# RGBM-03.net
KiCad netlist of a schematic drawn in Altium Designer
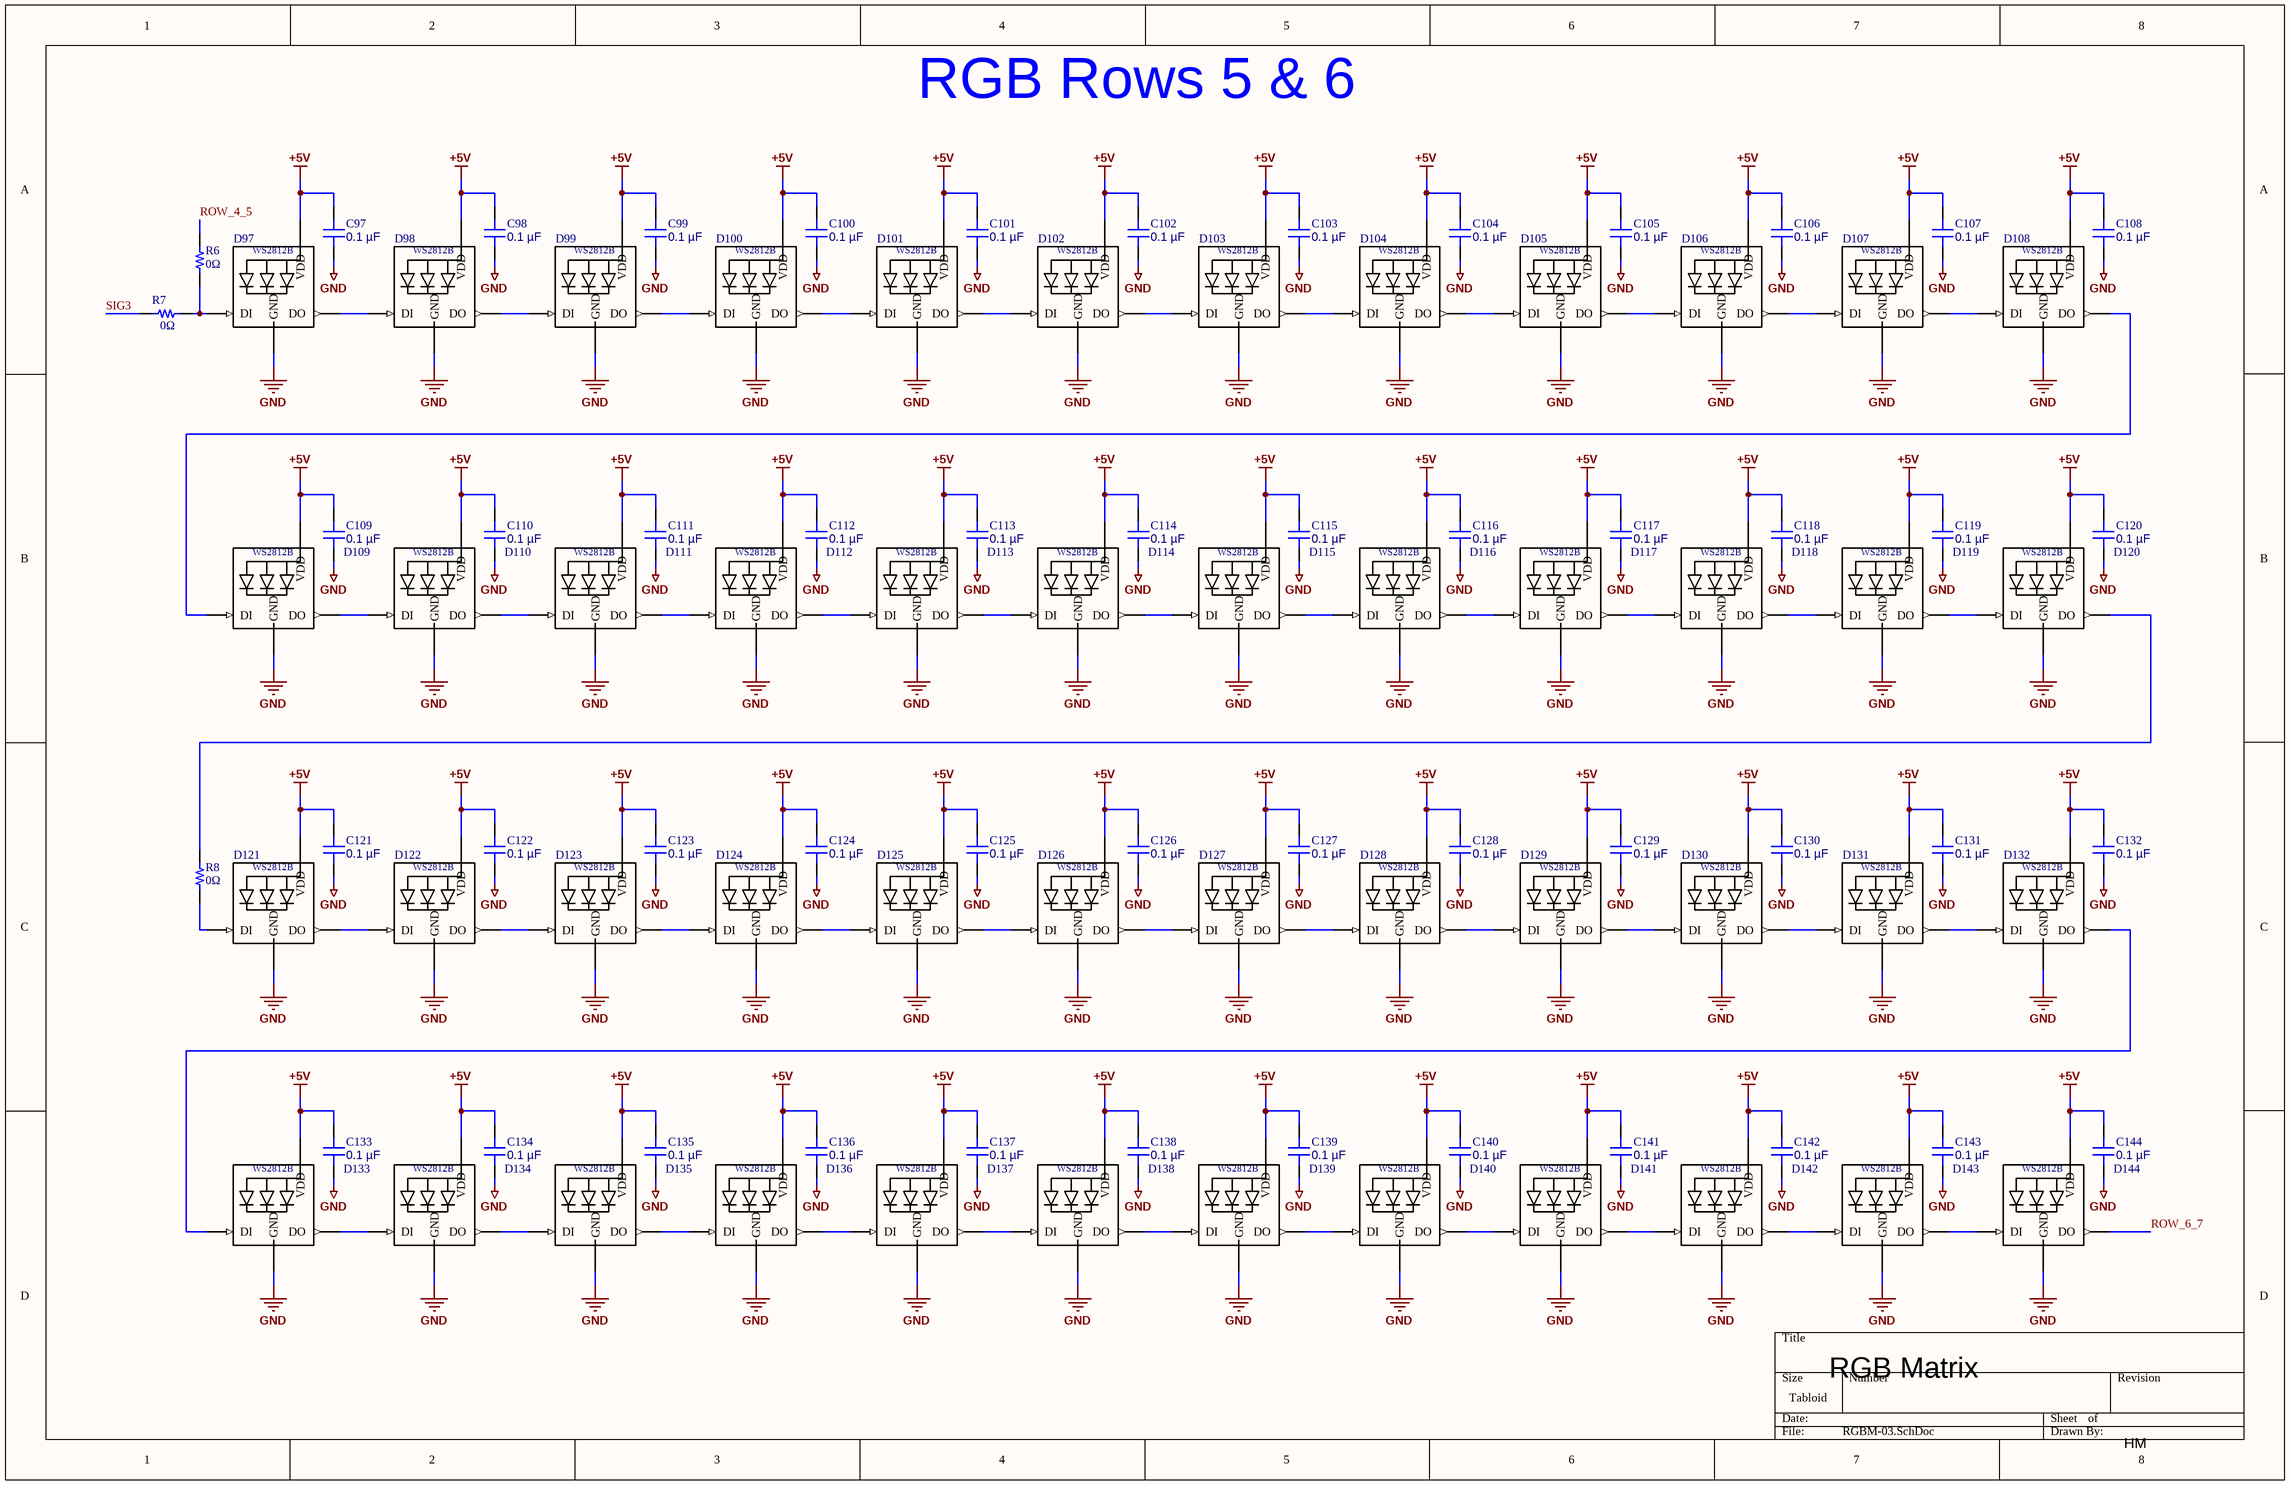
[diagram p0: RGBM-03.SchDoc]

(export (version "E")
  (design (tool "Eeschema 10.0.6"))
  (components
    (comp (ref "C97")
      (value "0.1 µF")
      (footprint "CAP 0603_1608")
      (description "CAP CER 0.1UF 50V X7R 0603")
      (fields
        (field (name "PART NUMBER") "C0603C104K5RAC7411")
        (field (name "CAPACITANCE") "0.1 µF")
        (field (name "MANUFACTURER") "KEMET")
      )
      (libsource (lib "Celestial Altium Library - altium_library") (part "Capacitor"))
    )
    (comp (ref "C98")
      (value "0.1 µF")
      (footprint "CAP 0603_1608")
      (description "CAP CER 0.1UF 50V X7R 0603")
      (fields
        (field (name "PART NUMBER") "C0603C104K5RAC7411")
        (field (name "CAPACITANCE") "0.1 µF")
        (field (name "MANUFACTURER") "KEMET")
      )
      (libsource (lib "Celestial Altium Library - altium_library") (part "Capacitor"))
    )
    (comp (ref "C99")
      (value "0.1 µF")
      (footprint "CAP 0603_1608")
      (description "CAP CER 0.1UF 50V X7R 0603")
      (fields
        (field (name "PART NUMBER") "C0603C104K5RAC7411")
        (field (name "CAPACITANCE") "0.1 µF")
        (field (name "MANUFACTURER") "KEMET")
      )
      (libsource (lib "Celestial Altium Library - altium_library") (part "Capacitor"))
    )
    (comp (ref "C100")
      (value "0.1 µF")
      (footprint "CAP 0603_1608")
      (description "CAP CER 0.1UF 50V X7R 0603")
      (fields
        (field (name "PART NUMBER") "C0603C104K5RAC7411")
        (field (name "CAPACITANCE") "0.1 µF")
        (field (name "MANUFACTURER") "KEMET")
      )
      (libsource (lib "Celestial Altium Library - altium_library") (part "Capacitor"))
    )
    (comp (ref "C101")
      (value "0.1 µF")
      (footprint "CAP 0603_1608")
      (description "CAP CER 0.1UF 50V X7R 0603")
      (fields
        (field (name "PART NUMBER") "C0603C104K5RAC7411")
        (field (name "CAPACITANCE") "0.1 µF")
        (field (name "MANUFACTURER") "KEMET")
      )
      (libsource (lib "Celestial Altium Library - altium_library") (part "Capacitor"))
    )
    (comp (ref "C102")
      (value "0.1 µF")
      (footprint "CAP 0603_1608")
      (description "CAP CER 0.1UF 50V X7R 0603")
      (fields
        (field (name "PART NUMBER") "C0603C104K5RAC7411")
        (field (name "CAPACITANCE") "0.1 µF")
        (field (name "MANUFACTURER") "KEMET")
      )
      (libsource (lib "Celestial Altium Library - altium_library") (part "Capacitor"))
    )
    (comp (ref "C103")
      (value "0.1 µF")
      (footprint "CAP 0603_1608")
      (description "CAP CER 0.1UF 50V X7R 0603")
      (fields
        (field (name "PART NUMBER") "C0603C104K5RAC7411")
        (field (name "CAPACITANCE") "0.1 µF")
        (field (name "MANUFACTURER") "KEMET")
      )
      (libsource (lib "Celestial Altium Library - altium_library") (part "Capacitor"))
    )
    (comp (ref "C104")
      (value "0.1 µF")
      (footprint "CAP 0603_1608")
      (description "CAP CER 0.1UF 50V X7R 0603")
      (fields
        (field (name "PART NUMBER") "C0603C104K5RAC7411")
        (field (name "CAPACITANCE") "0.1 µF")
        (field (name "MANUFACTURER") "KEMET")
      )
      (libsource (lib "Celestial Altium Library - altium_library") (part "Capacitor"))
    )
    (comp (ref "C105")
      (value "0.1 µF")
      (footprint "CAP 0603_1608")
      (description "CAP CER 0.1UF 50V X7R 0603")
      (fields
        (field (name "PART NUMBER") "C0603C104K5RAC7411")
        (field (name "CAPACITANCE") "0.1 µF")
        (field (name "MANUFACTURER") "KEMET")
      )
      (libsource (lib "Celestial Altium Library - altium_library") (part "Capacitor"))
    )
    (comp (ref "C106")
      (value "0.1 µF")
      (footprint "CAP 0603_1608")
      (description "CAP CER 0.1UF 50V X7R 0603")
      (fields
        (field (name "PART NUMBER") "C0603C104K5RAC7411")
        (field (name "CAPACITANCE") "0.1 µF")
        (field (name "MANUFACTURER") "KEMET")
      )
      (libsource (lib "Celestial Altium Library - altium_library") (part "Capacitor"))
    )
    (comp (ref "C107")
      (value "0.1 µF")
      (footprint "CAP 0603_1608")
      (description "CAP CER 0.1UF 50V X7R 0603")
      (fields
        (field (name "PART NUMBER") "C0603C104K5RAC7411")
        (field (name "CAPACITANCE") "0.1 µF")
        (field (name "MANUFACTURER") "KEMET")
      )
      (libsource (lib "Celestial Altium Library - altium_library") (part "Capacitor"))
    )
    (comp (ref "C108")
      (value "0.1 µF")
      (footprint "CAP 0603_1608")
      (description "CAP CER 0.1UF 50V X7R 0603")
      (fields
        (field (name "PART NUMBER") "C0603C104K5RAC7411")
        (field (name "CAPACITANCE") "0.1 µF")
        (field (name "MANUFACTURER") "KEMET")
      )
      (libsource (lib "Celestial Altium Library - altium_library") (part "Capacitor"))
    )
    (comp (ref "C109")
      (value "0.1 µF")
      (footprint "CAP 0603_1608")
      (description "CAP CER 0.1UF 50V X7R 0603")
      (fields
        (field (name "PART NUMBER") "C0603C104K5RAC7411")
        (field (name "CAPACITANCE") "0.1 µF")
        (field (name "MANUFACTURER") "KEMET")
      )
      (libsource (lib "Celestial Altium Library - altium_library") (part "Capacitor"))
    )
    (comp (ref "C110")
      (value "0.1 µF")
      (footprint "CAP 0603_1608")
      (description "CAP CER 0.1UF 50V X7R 0603")
      (fields
        (field (name "PART NUMBER") "C0603C104K5RAC7411")
        (field (name "CAPACITANCE") "0.1 µF")
        (field (name "MANUFACTURER") "KEMET")
      )
      (libsource (lib "Celestial Altium Library - altium_library") (part "Capacitor"))
    )
    (comp (ref "C111")
      (value "0.1 µF")
      (footprint "CAP 0603_1608")
      (description "CAP CER 0.1UF 50V X7R 0603")
      (fields
        (field (name "PART NUMBER") "C0603C104K5RAC7411")
        (field (name "CAPACITANCE") "0.1 µF")
        (field (name "MANUFACTURER") "KEMET")
      )
      (libsource (lib "Celestial Altium Library - altium_library") (part "Capacitor"))
    )
    (comp (ref "C112")
      (value "0.1 µF")
      (footprint "CAP 0603_1608")
      (description "CAP CER 0.1UF 50V X7R 0603")
      (fields
        (field (name "PART NUMBER") "C0603C104K5RAC7411")
        (field (name "CAPACITANCE") "0.1 µF")
        (field (name "MANUFACTURER") "KEMET")
      )
      (libsource (lib "Celestial Altium Library - altium_library") (part "Capacitor"))
    )
    (comp (ref "C113")
      (value "0.1 µF")
      (footprint "CAP 0603_1608")
      (description "CAP CER 0.1UF 50V X7R 0603")
      (fields
        (field (name "PART NUMBER") "C0603C104K5RAC7411")
        (field (name "CAPACITANCE") "0.1 µF")
        (field (name "MANUFACTURER") "KEMET")
      )
      (libsource (lib "Celestial Altium Library - altium_library") (part "Capacitor"))
    )
    (comp (ref "C114")
      (value "0.1 µF")
      (footprint "CAP 0603_1608")
      (description "CAP CER 0.1UF 50V X7R 0603")
      (fields
        (field (name "PART NUMBER") "C0603C104K5RAC7411")
        (field (name "CAPACITANCE") "0.1 µF")
        (field (name "MANUFACTURER") "KEMET")
      )
      (libsource (lib "Celestial Altium Library - altium_library") (part "Capacitor"))
    )
    (comp (ref "C115")
      (value "0.1 µF")
      (footprint "CAP 0603_1608")
      (description "CAP CER 0.1UF 50V X7R 0603")
      (fields
        (field (name "PART NUMBER") "C0603C104K5RAC7411")
        (field (name "CAPACITANCE") "0.1 µF")
        (field (name "MANUFACTURER") "KEMET")
      )
      (libsource (lib "Celestial Altium Library - altium_library") (part "Capacitor"))
    )
    (comp (ref "C116")
      (value "0.1 µF")
      (footprint "CAP 0603_1608")
      (description "CAP CER 0.1UF 50V X7R 0603")
      (fields
        (field (name "PART NUMBER") "C0603C104K5RAC7411")
        (field (name "CAPACITANCE") "0.1 µF")
        (field (name "MANUFACTURER") "KEMET")
      )
      (libsource (lib "Celestial Altium Library - altium_library") (part "Capacitor"))
    )
    (comp (ref "C117")
      (value "0.1 µF")
      (footprint "CAP 0603_1608")
      (description "CAP CER 0.1UF 50V X7R 0603")
      (fields
        (field (name "PART NUMBER") "C0603C104K5RAC7411")
        (field (name "CAPACITANCE") "0.1 µF")
        (field (name "MANUFACTURER") "KEMET")
      )
      (libsource (lib "Celestial Altium Library - altium_library") (part "Capacitor"))
    )
    (comp (ref "C118")
      (value "0.1 µF")
      (footprint "CAP 0603_1608")
      (description "CAP CER 0.1UF 50V X7R 0603")
      (fields
        (field (name "PART NUMBER") "C0603C104K5RAC7411")
        (field (name "CAPACITANCE") "0.1 µF")
        (field (name "MANUFACTURER") "KEMET")
      )
      (libsource (lib "Celestial Altium Library - altium_library") (part "Capacitor"))
    )
    (comp (ref "C119")
      (value "0.1 µF")
      (footprint "CAP 0603_1608")
      (description "CAP CER 0.1UF 50V X7R 0603")
      (fields
        (field (name "PART NUMBER") "C0603C104K5RAC7411")
        (field (name "CAPACITANCE") "0.1 µF")
        (field (name "MANUFACTURER") "KEMET")
      )
      (libsource (lib "Celestial Altium Library - altium_library") (part "Capacitor"))
    )
    (comp (ref "C120")
      (value "0.1 µF")
      (footprint "CAP 0603_1608")
      (description "CAP CER 0.1UF 50V X7R 0603")
      (fields
        (field (name "PART NUMBER") "C0603C104K5RAC7411")
        (field (name "CAPACITANCE") "0.1 µF")
        (field (name "MANUFACTURER") "KEMET")
      )
      (libsource (lib "Celestial Altium Library - altium_library") (part "Capacitor"))
    )
    (comp (ref "C121")
      (value "0.1 µF")
      (footprint "CAP 0603_1608")
      (description "CAP CER 0.1UF 50V X7R 0603")
      (fields
        (field (name "PART NUMBER") "C0603C104K5RAC7411")
        (field (name "CAPACITANCE") "0.1 µF")
        (field (name "MANUFACTURER") "KEMET")
      )
      (libsource (lib "Celestial Altium Library - altium_library") (part "Capacitor"))
    )
    (comp (ref "C122")
      (value "0.1 µF")
      (footprint "CAP 0603_1608")
      (description "CAP CER 0.1UF 50V X7R 0603")
      (fields
        (field (name "PART NUMBER") "C0603C104K5RAC7411")
        (field (name "CAPACITANCE") "0.1 µF")
        (field (name "MANUFACTURER") "KEMET")
      )
      (libsource (lib "Celestial Altium Library - altium_library") (part "Capacitor"))
    )
    (comp (ref "C123")
      (value "0.1 µF")
      (footprint "CAP 0603_1608")
      (description "CAP CER 0.1UF 50V X7R 0603")
      (fields
        (field (name "PART NUMBER") "C0603C104K5RAC7411")
        (field (name "CAPACITANCE") "0.1 µF")
        (field (name "MANUFACTURER") "KEMET")
      )
      (libsource (lib "Celestial Altium Library - altium_library") (part "Capacitor"))
    )
    (comp (ref "C124")
      (value "0.1 µF")
      (footprint "CAP 0603_1608")
      (description "CAP CER 0.1UF 50V X7R 0603")
      (fields
        (field (name "PART NUMBER") "C0603C104K5RAC7411")
        (field (name "CAPACITANCE") "0.1 µF")
        (field (name "MANUFACTURER") "KEMET")
      )
      (libsource (lib "Celestial Altium Library - altium_library") (part "Capacitor"))
    )
    (comp (ref "C125")
      (value "0.1 µF")
      (footprint "CAP 0603_1608")
      (description "CAP CER 0.1UF 50V X7R 0603")
      (fields
        (field (name "PART NUMBER") "C0603C104K5RAC7411")
        (field (name "CAPACITANCE") "0.1 µF")
        (field (name "MANUFACTURER") "KEMET")
      )
      (libsource (lib "Celestial Altium Library - altium_library") (part "Capacitor"))
    )
    (comp (ref "C126")
      (value "0.1 µF")
      (footprint "CAP 0603_1608")
      (description "CAP CER 0.1UF 50V X7R 0603")
      (fields
        (field (name "PART NUMBER") "C0603C104K5RAC7411")
        (field (name "CAPACITANCE") "0.1 µF")
        (field (name "MANUFACTURER") "KEMET")
      )
      (libsource (lib "Celestial Altium Library - altium_library") (part "Capacitor"))
    )
    (comp (ref "C127")
      (value "0.1 µF")
      (footprint "CAP 0603_1608")
      (description "CAP CER 0.1UF 50V X7R 0603")
      (fields
        (field (name "PART NUMBER") "C0603C104K5RAC7411")
        (field (name "CAPACITANCE") "0.1 µF")
        (field (name "MANUFACTURER") "KEMET")
      )
      (libsource (lib "Celestial Altium Library - altium_library") (part "Capacitor"))
    )
    (comp (ref "C128")
      (value "0.1 µF")
      (footprint "CAP 0603_1608")
      (description "CAP CER 0.1UF 50V X7R 0603")
      (fields
        (field (name "PART NUMBER") "C0603C104K5RAC7411")
        (field (name "CAPACITANCE") "0.1 µF")
        (field (name "MANUFACTURER") "KEMET")
      )
      (libsource (lib "Celestial Altium Library - altium_library") (part "Capacitor"))
    )
    (comp (ref "C129")
      (value "0.1 µF")
      (footprint "CAP 0603_1608")
      (description "CAP CER 0.1UF 50V X7R 0603")
      (fields
        (field (name "PART NUMBER") "C0603C104K5RAC7411")
        (field (name "CAPACITANCE") "0.1 µF")
        (field (name "MANUFACTURER") "KEMET")
      )
      (libsource (lib "Celestial Altium Library - altium_library") (part "Capacitor"))
    )
    (comp (ref "C130")
      (value "0.1 µF")
      (footprint "CAP 0603_1608")
      (description "CAP CER 0.1UF 50V X7R 0603")
      (fields
        (field (name "PART NUMBER") "C0603C104K5RAC7411")
        (field (name "CAPACITANCE") "0.1 µF")
        (field (name "MANUFACTURER") "KEMET")
      )
      (libsource (lib "Celestial Altium Library - altium_library") (part "Capacitor"))
    )
    (comp (ref "C131")
      (value "0.1 µF")
      (footprint "CAP 0603_1608")
      (description "CAP CER 0.1UF 50V X7R 0603")
      (fields
        (field (name "PART NUMBER") "C0603C104K5RAC7411")
        (field (name "CAPACITANCE") "0.1 µF")
        (field (name "MANUFACTURER") "KEMET")
      )
      (libsource (lib "Celestial Altium Library - altium_library") (part "Capacitor"))
    )
    (comp (ref "C132")
      (value "0.1 µF")
      (footprint "CAP 0603_1608")
      (description "CAP CER 0.1UF 50V X7R 0603")
      (fields
        (field (name "PART NUMBER") "C0603C104K5RAC7411")
        (field (name "CAPACITANCE") "0.1 µF")
        (field (name "MANUFACTURER") "KEMET")
      )
      (libsource (lib "Celestial Altium Library - altium_library") (part "Capacitor"))
    )
    (comp (ref "C133")
      (value "0.1 µF")
      (footprint "CAP 0603_1608")
      (description "CAP CER 0.1UF 50V X7R 0603")
      (fields
        (field (name "PART NUMBER") "C0603C104K5RAC7411")
        (field (name "CAPACITANCE") "0.1 µF")
        (field (name "MANUFACTURER") "KEMET")
      )
      (libsource (lib "Celestial Altium Library - altium_library") (part "Capacitor"))
    )
    (comp (ref "C134")
      (value "0.1 µF")
      (footprint "CAP 0603_1608")
      (description "CAP CER 0.1UF 50V X7R 0603")
      (fields
        (field (name "PART NUMBER") "C0603C104K5RAC7411")
        (field (name "CAPACITANCE") "0.1 µF")
        (field (name "MANUFACTURER") "KEMET")
      )
      (libsource (lib "Celestial Altium Library - altium_library") (part "Capacitor"))
    )
    (comp (ref "C135")
      (value "0.1 µF")
      (footprint "CAP 0603_1608")
      (description "CAP CER 0.1UF 50V X7R 0603")
      (fields
        (field (name "PART NUMBER") "C0603C104K5RAC7411")
        (field (name "CAPACITANCE") "0.1 µF")
        (field (name "MANUFACTURER") "KEMET")
      )
      (libsource (lib "Celestial Altium Library - altium_library") (part "Capacitor"))
    )
    (comp (ref "C136")
      (value "0.1 µF")
      (footprint "CAP 0603_1608")
      (description "CAP CER 0.1UF 50V X7R 0603")
      (fields
        (field (name "PART NUMBER") "C0603C104K5RAC7411")
        (field (name "CAPACITANCE") "0.1 µF")
        (field (name "MANUFACTURER") "KEMET")
      )
      (libsource (lib "Celestial Altium Library - altium_library") (part "Capacitor"))
    )
    (comp (ref "C137")
      (value "0.1 µF")
      (footprint "CAP 0603_1608")
      (description "CAP CER 0.1UF 50V X7R 0603")
      (fields
        (field (name "PART NUMBER") "C0603C104K5RAC7411")
        (field (name "CAPACITANCE") "0.1 µF")
        (field (name "MANUFACTURER") "KEMET")
      )
      (libsource (lib "Celestial Altium Library - altium_library") (part "Capacitor"))
    )
    (comp (ref "C138")
      (value "0.1 µF")
      (footprint "CAP 0603_1608")
      (description "CAP CER 0.1UF 50V X7R 0603")
      (fields
        (field (name "PART NUMBER") "C0603C104K5RAC7411")
        (field (name "CAPACITANCE") "0.1 µF")
        (field (name "MANUFACTURER") "KEMET")
      )
      (libsource (lib "Celestial Altium Library - altium_library") (part "Capacitor"))
    )
    (comp (ref "C139")
      (value "0.1 µF")
      (footprint "CAP 0603_1608")
      (description "CAP CER 0.1UF 50V X7R 0603")
      (fields
        (field (name "PART NUMBER") "C0603C104K5RAC7411")
        (field (name "CAPACITANCE") "0.1 µF")
        (field (name "MANUFACTURER") "KEMET")
      )
      (libsource (lib "Celestial Altium Library - altium_library") (part "Capacitor"))
    )
    (comp (ref "C140")
      (value "0.1 µF")
      (footprint "CAP 0603_1608")
      (description "CAP CER 0.1UF 50V X7R 0603")
      (fields
        (field (name "PART NUMBER") "C0603C104K5RAC7411")
        (field (name "CAPACITANCE") "0.1 µF")
        (field (name "MANUFACTURER") "KEMET")
      )
      (libsource (lib "Celestial Altium Library - altium_library") (part "Capacitor"))
    )
    (comp (ref "C141")
      (value "0.1 µF")
      (footprint "CAP 0603_1608")
      (description "CAP CER 0.1UF 50V X7R 0603")
      (fields
        (field (name "PART NUMBER") "C0603C104K5RAC7411")
        (field (name "CAPACITANCE") "0.1 µF")
        (field (name "MANUFACTURER") "KEMET")
      )
      (libsource (lib "Celestial Altium Library - altium_library") (part "Capacitor"))
    )
    (comp (ref "C142")
      (value "0.1 µF")
      (footprint "CAP 0603_1608")
      (description "CAP CER 0.1UF 50V X7R 0603")
      (fields
        (field (name "PART NUMBER") "C0603C104K5RAC7411")
        (field (name "CAPACITANCE") "0.1 µF")
        (field (name "MANUFACTURER") "KEMET")
      )
      (libsource (lib "Celestial Altium Library - altium_library") (part "Capacitor"))
    )
    (comp (ref "C143")
      (value "0.1 µF")
      (footprint "CAP 0603_1608")
      (description "CAP CER 0.1UF 50V X7R 0603")
      (fields
        (field (name "PART NUMBER") "C0603C104K5RAC7411")
        (field (name "CAPACITANCE") "0.1 µF")
        (field (name "MANUFACTURER") "KEMET")
      )
      (libsource (lib "Celestial Altium Library - altium_library") (part "Capacitor"))
    )
    (comp (ref "C144")
      (value "0.1 µF")
      (footprint "CAP 0603_1608")
      (description "CAP CER 0.1UF 50V X7R 0603")
      (fields
        (field (name "PART NUMBER") "C0603C104K5RAC7411")
        (field (name "CAPACITANCE") "0.1 µF")
        (field (name "MANUFACTURER") "KEMET")
      )
      (libsource (lib "Celestial Altium Library - altium_library") (part "Capacitor"))
    )
    (comp (ref "D97")
      (value "WS2812B")
      (footprint "*WS2812B_WS2812B(Primary)")
      (description "Intelligent control LED integrated light source")
      (fields (field (name "MF") "Worldsemi"))
      (libsource (lib "WS2812B") (part "WS2812B"))
    )
    (comp (ref "D98")
      (value "WS2812B")
      (footprint "*WS2812B_WS2812B(Primary)")
      (description "Intelligent control LED integrated light source")
      (fields (field (name "MF") "Worldsemi"))
      (libsource (lib "WS2812B") (part "WS2812B"))
    )
    (comp (ref "D99")
      (value "WS2812B")
      (footprint "*WS2812B_WS2812B(Primary)")
      (description "Intelligent control LED integrated light source")
      (fields (field (name "MF") "Worldsemi"))
      (libsource (lib "WS2812B") (part "WS2812B"))
    )
    (comp (ref "D100")
      (value "WS2812B")
      (footprint "*WS2812B_WS2812B(Primary)")
      (description "Intelligent control LED integrated light source")
      (fields (field (name "MF") "Worldsemi"))
      (libsource (lib "WS2812B") (part "WS2812B"))
    )
    (comp (ref "D101")
      (value "WS2812B")
      (footprint "*WS2812B_WS2812B(Primary)")
      (description "Intelligent control LED integrated light source")
      (fields (field (name "MF") "Worldsemi"))
      (libsource (lib "WS2812B") (part "WS2812B"))
    )
    (comp (ref "D102")
      (value "WS2812B")
      (footprint "*WS2812B_WS2812B(Primary)")
      (description "Intelligent control LED integrated light source")
      (fields (field (name "MF") "Worldsemi"))
      (libsource (lib "WS2812B") (part "WS2812B"))
    )
    (comp (ref "D103")
      (value "WS2812B")
      (footprint "*WS2812B_WS2812B(Primary)")
      (description "Intelligent control LED integrated light source")
      (fields (field (name "MF") "Worldsemi"))
      (libsource (lib "WS2812B") (part "WS2812B"))
    )
    (comp (ref "D104")
      (value "WS2812B")
      (footprint "*WS2812B_WS2812B(Primary)")
      (description "Intelligent control LED integrated light source")
      (fields (field (name "MF") "Worldsemi"))
      (libsource (lib "WS2812B") (part "WS2812B"))
    )
    (comp (ref "D105")
      (value "WS2812B")
      (footprint "*WS2812B_WS2812B(Primary)")
      (description "Intelligent control LED integrated light source")
      (fields (field (name "MF") "Worldsemi"))
      (libsource (lib "WS2812B") (part "WS2812B"))
    )
    (comp (ref "D106")
      (value "WS2812B")
      (footprint "*WS2812B_WS2812B(Primary)")
      (description "Intelligent control LED integrated light source")
      (fields (field (name "MF") "Worldsemi"))
      (libsource (lib "WS2812B") (part "WS2812B"))
    )
    (comp (ref "D107")
      (value "WS2812B")
      (footprint "*WS2812B_WS2812B(Primary)")
      (description "Intelligent control LED integrated light source")
      (fields (field (name "MF") "Worldsemi"))
      (libsource (lib "WS2812B") (part "WS2812B"))
    )
    (comp (ref "D108")
      (value "WS2812B")
      (footprint "*WS2812B_WS2812B(Primary)")
      (description "Intelligent control LED integrated light source")
      (fields (field (name "MF") "Worldsemi"))
      (libsource (lib "WS2812B") (part "WS2812B"))
    )
    (comp (ref "D109")
      (value "WS2812B")
      (footprint "*WS2812B_WS2812B(Primary)")
      (description "Intelligent control LED integrated light source")
      (fields (field (name "MF") "Worldsemi"))
      (libsource (lib "WS2812B") (part "WS2812B"))
    )
    (comp (ref "D110")
      (value "WS2812B")
      (footprint "*WS2812B_WS2812B(Primary)")
      (description "Intelligent control LED integrated light source")
      (fields (field (name "MF") "Worldsemi"))
      (libsource (lib "WS2812B") (part "WS2812B"))
    )
    (comp (ref "D111")
      (value "WS2812B")
      (footprint "*WS2812B_WS2812B(Primary)")
      (description "Intelligent control LED integrated light source")
      (fields (field (name "MF") "Worldsemi"))
      (libsource (lib "WS2812B") (part "WS2812B"))
    )
    (comp (ref "D112")
      (value "WS2812B")
      (footprint "*WS2812B_WS2812B(Primary)")
      (description "Intelligent control LED integrated light source")
      (fields (field (name "MF") "Worldsemi"))
      (libsource (lib "WS2812B") (part "WS2812B"))
    )
    (comp (ref "D113")
      (value "WS2812B")
      (footprint "*WS2812B_WS2812B(Primary)")
      (description "Intelligent control LED integrated light source")
      (fields (field (name "MF") "Worldsemi"))
      (libsource (lib "WS2812B") (part "WS2812B"))
    )
    (comp (ref "D114")
      (value "WS2812B")
      (footprint "*WS2812B_WS2812B(Primary)")
      (description "Intelligent control LED integrated light source")
      (fields (field (name "MF") "Worldsemi"))
      (libsource (lib "WS2812B") (part "WS2812B"))
    )
    (comp (ref "D115")
      (value "WS2812B")
      (footprint "*WS2812B_WS2812B(Primary)")
      (description "Intelligent control LED integrated light source")
      (fields (field (name "MF") "Worldsemi"))
      (libsource (lib "WS2812B") (part "WS2812B"))
    )
    (comp (ref "D116")
      (value "WS2812B")
      (footprint "*WS2812B_WS2812B(Primary)")
      (description "Intelligent control LED integrated light source")
      (fields (field (name "MF") "Worldsemi"))
      (libsource (lib "WS2812B") (part "WS2812B"))
    )
    (comp (ref "D117")
      (value "WS2812B")
      (footprint "*WS2812B_WS2812B(Primary)")
      (description "Intelligent control LED integrated light source")
      (fields (field (name "MF") "Worldsemi"))
      (libsource (lib "WS2812B") (part "WS2812B"))
    )
    (comp (ref "D118")
      (value "WS2812B")
      (footprint "*WS2812B_WS2812B(Primary)")
      (description "Intelligent control LED integrated light source")
      (fields (field (name "MF") "Worldsemi"))
      (libsource (lib "WS2812B") (part "WS2812B"))
    )
    (comp (ref "D119")
      (value "WS2812B")
      (footprint "*WS2812B_WS2812B(Primary)")
      (description "Intelligent control LED integrated light source")
      (fields (field (name "MF") "Worldsemi"))
      (libsource (lib "WS2812B") (part "WS2812B"))
    )
    (comp (ref "D120")
      (value "WS2812B")
      (footprint "*WS2812B_WS2812B(Primary)")
      (description "Intelligent control LED integrated light source")
      (fields (field (name "MF") "Worldsemi"))
      (libsource (lib "WS2812B") (part "WS2812B"))
    )
    (comp (ref "D121")
      (value "WS2812B")
      (footprint "*WS2812B_WS2812B(Primary)")
      (description "Intelligent control LED integrated light source")
      (fields (field (name "MF") "Worldsemi"))
      (libsource (lib "WS2812B") (part "WS2812B"))
    )
    (comp (ref "D122")
      (value "WS2812B")
      (footprint "*WS2812B_WS2812B(Primary)")
      (description "Intelligent control LED integrated light source")
      (fields (field (name "MF") "Worldsemi"))
      (libsource (lib "WS2812B") (part "WS2812B"))
    )
    (comp (ref "D123")
      (value "WS2812B")
      (footprint "*WS2812B_WS2812B(Primary)")
      (description "Intelligent control LED integrated light source")
      (fields (field (name "MF") "Worldsemi"))
      (libsource (lib "WS2812B") (part "WS2812B"))
    )
    (comp (ref "D124")
      (value "WS2812B")
      (footprint "*WS2812B_WS2812B(Primary)")
      (description "Intelligent control LED integrated light source")
      (fields (field (name "MF") "Worldsemi"))
      (libsource (lib "WS2812B") (part "WS2812B"))
    )
    (comp (ref "D125")
      (value "WS2812B")
      (footprint "*WS2812B_WS2812B(Primary)")
      (description "Intelligent control LED integrated light source")
      (fields (field (name "MF") "Worldsemi"))
      (libsource (lib "WS2812B") (part "WS2812B"))
    )
    (comp (ref "D126")
      (value "WS2812B")
      (footprint "*WS2812B_WS2812B(Primary)")
      (description "Intelligent control LED integrated light source")
      (fields (field (name "MF") "Worldsemi"))
      (libsource (lib "WS2812B") (part "WS2812B"))
    )
    (comp (ref "D127")
      (value "WS2812B")
      (footprint "*WS2812B_WS2812B(Primary)")
      (description "Intelligent control LED integrated light source")
      (fields (field (name "MF") "Worldsemi"))
      (libsource (lib "WS2812B") (part "WS2812B"))
    )
    (comp (ref "D128")
      (value "WS2812B")
      (footprint "*WS2812B_WS2812B(Primary)")
      (description "Intelligent control LED integrated light source")
      (fields (field (name "MF") "Worldsemi"))
      (libsource (lib "WS2812B") (part "WS2812B"))
    )
    (comp (ref "D129")
      (value "WS2812B")
      (footprint "*WS2812B_WS2812B(Primary)")
      (description "Intelligent control LED integrated light source")
      (fields (field (name "MF") "Worldsemi"))
      (libsource (lib "WS2812B") (part "WS2812B"))
    )
    (comp (ref "D130")
      (value "WS2812B")
      (footprint "*WS2812B_WS2812B(Primary)")
      (description "Intelligent control LED integrated light source")
      (fields (field (name "MF") "Worldsemi"))
      (libsource (lib "WS2812B") (part "WS2812B"))
    )
    (comp (ref "D131")
      (value "WS2812B")
      (footprint "*WS2812B_WS2812B(Primary)")
      (description "Intelligent control LED integrated light source")
      (fields (field (name "MF") "Worldsemi"))
      (libsource (lib "WS2812B") (part "WS2812B"))
    )
    (comp (ref "D132")
      (value "WS2812B")
      (footprint "*WS2812B_WS2812B(Primary)")
      (description "Intelligent control LED integrated light source")
      (fields (field (name "MF") "Worldsemi"))
      (libsource (lib "WS2812B") (part "WS2812B"))
    )
    (comp (ref "D133")
      (value "WS2812B")
      (footprint "*WS2812B_WS2812B(Primary)")
      (description "Intelligent control LED integrated light source")
      (fields (field (name "MF") "Worldsemi"))
      (libsource (lib "WS2812B") (part "WS2812B"))
    )
    (comp (ref "D134")
      (value "WS2812B")
      (footprint "*WS2812B_WS2812B(Primary)")
      (description "Intelligent control LED integrated light source")
      (fields (field (name "MF") "Worldsemi"))
      (libsource (lib "WS2812B") (part "WS2812B"))
    )
    (comp (ref "D135")
      (value "WS2812B")
      (footprint "*WS2812B_WS2812B(Primary)")
      (description "Intelligent control LED integrated light source")
      (fields (field (name "MF") "Worldsemi"))
      (libsource (lib "WS2812B") (part "WS2812B"))
    )
    (comp (ref "D136")
      (value "WS2812B")
      (footprint "*WS2812B_WS2812B(Primary)")
      (description "Intelligent control LED integrated light source")
      (fields (field (name "MF") "Worldsemi"))
      (libsource (lib "WS2812B") (part "WS2812B"))
    )
    (comp (ref "D137")
      (value "WS2812B")
      (footprint "*WS2812B_WS2812B(Primary)")
      (description "Intelligent control LED integrated light source")
      (fields (field (name "MF") "Worldsemi"))
      (libsource (lib "WS2812B") (part "WS2812B"))
    )
    (comp (ref "D138")
      (value "WS2812B")
      (footprint "*WS2812B_WS2812B(Primary)")
      (description "Intelligent control LED integrated light source")
      (fields (field (name "MF") "Worldsemi"))
      (libsource (lib "WS2812B") (part "WS2812B"))
    )
    (comp (ref "D139")
      (value "WS2812B")
      (footprint "*WS2812B_WS2812B(Primary)")
      (description "Intelligent control LED integrated light source")
      (fields (field (name "MF") "Worldsemi"))
      (libsource (lib "WS2812B") (part "WS2812B"))
    )
    (comp (ref "D140")
      (value "WS2812B")
      (footprint "*WS2812B_WS2812B(Primary)")
      (description "Intelligent control LED integrated light source")
      (fields (field (name "MF") "Worldsemi"))
      (libsource (lib "WS2812B") (part "WS2812B"))
    )
    (comp (ref "D141")
      (value "WS2812B")
      (footprint "*WS2812B_WS2812B(Primary)")
      (description "Intelligent control LED integrated light source")
      (fields (field (name "MF") "Worldsemi"))
      (libsource (lib "WS2812B") (part "WS2812B"))
    )
    (comp (ref "D142")
      (value "WS2812B")
      (footprint "*WS2812B_WS2812B(Primary)")
      (description "Intelligent control LED integrated light source")
      (fields (field (name "MF") "Worldsemi"))
      (libsource (lib "WS2812B") (part "WS2812B"))
    )
    (comp (ref "D143")
      (value "WS2812B")
      (footprint "*WS2812B_WS2812B(Primary)")
      (description "Intelligent control LED integrated light source")
      (fields (field (name "MF") "Worldsemi"))
      (libsource (lib "WS2812B") (part "WS2812B"))
    )
    (comp (ref "D144")
      (value "WS2812B")
      (footprint "*WS2812B_WS2812B(Primary)")
      (description "Intelligent control LED integrated light source")
      (fields (field (name "MF") "Worldsemi"))
      (libsource (lib "WS2812B") (part "WS2812B"))
    )
    (comp (ref "R6")
      (value "0Ω")
      (footprint "RES 0603_1608")
      (description "RES SMD 0 OHM JUMPER 0603")
      (fields (field (name "PART NUMBER") "YJP1608-R001") (field (name "MANUFACTURER") "Susumu"))
      (libsource (lib "Celestial Altium Library - altium_library") (part "Resistor"))
    )
    (comp (ref "R7")
      (value "0Ω")
      (footprint "RES 0603_1608")
      (description "RES SMD 0 OHM JUMPER 0603")
      (fields (field (name "PART NUMBER") "YJP1608-R001") (field (name "MANUFACTURER") "Susumu"))
      (libsource (lib "Celestial Altium Library - altium_library") (part "Resistor"))
    )
    (comp (ref "R8")
      (value "0Ω")
      (footprint "RES 0603_1608")
      (description "RES SMD 0 OHM JUMPER 0603")
      (fields (field (name "PART NUMBER") "YJP1608-R001") (field (name "MANUFACTURER") "Susumu"))
      (libsource (lib "Celestial Altium Library - altium_library") (part "Resistor"))
    )
  )
  (nets
    (net (code "1") (name "+5V") (class "Default")
      (node (ref "C100") (pin "2") (pinfunction "2_2") (pintype "passive"))
      (node (ref "C101") (pin "2") (pinfunction "2_2") (pintype "passive"))
      (node (ref "C102") (pin "2") (pinfunction "2_2") (pintype "passive"))
      (node (ref "C103") (pin "2") (pinfunction "2_2") (pintype "passive"))
      (node (ref "C104") (pin "2") (pinfunction "2_2") (pintype "passive"))
      (node (ref "C105") (pin "2") (pinfunction "2_2") (pintype "passive"))
      (node (ref "C106") (pin "2") (pinfunction "2_2") (pintype "passive"))
      (node (ref "C107") (pin "2") (pinfunction "2_2") (pintype "passive"))
      (node (ref "C108") (pin "2") (pinfunction "2_2") (pintype "passive"))
      (node (ref "C109") (pin "2") (pinfunction "2_2") (pintype "passive"))
      (node (ref "C110") (pin "2") (pinfunction "2_2") (pintype "passive"))
      (node (ref "C111") (pin "2") (pinfunction "2_2") (pintype "passive"))
      (node (ref "C112") (pin "2") (pinfunction "2_2") (pintype "passive"))
      (node (ref "C113") (pin "2") (pinfunction "2_2") (pintype "passive"))
      (node (ref "C114") (pin "2") (pinfunction "2_2") (pintype "passive"))
      (node (ref "C115") (pin "2") (pinfunction "2_2") (pintype "passive"))
      (node (ref "C116") (pin "2") (pinfunction "2_2") (pintype "passive"))
      (node (ref "C117") (pin "2") (pinfunction "2_2") (pintype "passive"))
      (node (ref "C118") (pin "2") (pinfunction "2_2") (pintype "passive"))
      (node (ref "C119") (pin "2") (pinfunction "2_2") (pintype "passive"))
      (node (ref "C120") (pin "2") (pinfunction "2_2") (pintype "passive"))
      (node (ref "C121") (pin "2") (pinfunction "2_2") (pintype "passive"))
      (node (ref "C122") (pin "2") (pinfunction "2_2") (pintype "passive"))
      (node (ref "C123") (pin "2") (pinfunction "2_2") (pintype "passive"))
      (node (ref "C124") (pin "2") (pinfunction "2_2") (pintype "passive"))
      (node (ref "C125") (pin "2") (pinfunction "2_2") (pintype "passive"))
      (node (ref "C126") (pin "2") (pinfunction "2_2") (pintype "passive"))
      (node (ref "C127") (pin "2") (pinfunction "2_2") (pintype "passive"))
      (node (ref "C128") (pin "2") (pinfunction "2_2") (pintype "passive"))
      (node (ref "C129") (pin "2") (pinfunction "2_2") (pintype "passive"))
      (node (ref "C130") (pin "2") (pinfunction "2_2") (pintype "passive"))
      (node (ref "C131") (pin "2") (pinfunction "2_2") (pintype "passive"))
      (node (ref "C132") (pin "2") (pinfunction "2_2") (pintype "passive"))
      (node (ref "C133") (pin "2") (pinfunction "2_2") (pintype "passive"))
      (node (ref "C134") (pin "2") (pinfunction "2_2") (pintype "passive"))
      (node (ref "C135") (pin "2") (pinfunction "2_2") (pintype "passive"))
      (node (ref "C136") (pin "2") (pinfunction "2_2") (pintype "passive"))
      (node (ref "C137") (pin "2") (pinfunction "2_2") (pintype "passive"))
      (node (ref "C138") (pin "2") (pinfunction "2_2") (pintype "passive"))
      (node (ref "C139") (pin "2") (pinfunction "2_2") (pintype "passive"))
      (node (ref "C140") (pin "2") (pinfunction "2_2") (pintype "passive"))
      (node (ref "C141") (pin "2") (pinfunction "2_2") (pintype "passive"))
      (node (ref "C142") (pin "2") (pinfunction "2_2") (pintype "passive"))
      (node (ref "C143") (pin "2") (pinfunction "2_2") (pintype "passive"))
      (node (ref "C144") (pin "2") (pinfunction "2_2") (pintype "passive"))
      (node (ref "C97") (pin "2") (pinfunction "2_2") (pintype "passive"))
      (node (ref "C98") (pin "2") (pinfunction "2_2") (pintype "passive"))
      (node (ref "C99") (pin "2") (pinfunction "2_2") (pintype "passive"))
      (node (ref "D100") (pin "1-VDD") (pinfunction "VDD_1-VDD") (pintype "power_in"))
      (node (ref "D101") (pin "1-VDD") (pinfunction "VDD_1-VDD") (pintype "power_in"))
      (node (ref "D102") (pin "1-VDD") (pinfunction "VDD_1-VDD") (pintype "power_in"))
      (node (ref "D103") (pin "1-VDD") (pinfunction "VDD_1-VDD") (pintype "power_in"))
      (node (ref "D104") (pin "1-VDD") (pinfunction "VDD_1-VDD") (pintype "power_in"))
      (node (ref "D105") (pin "1-VDD") (pinfunction "VDD_1-VDD") (pintype "power_in"))
      (node (ref "D106") (pin "1-VDD") (pinfunction "VDD_1-VDD") (pintype "power_in"))
      (node (ref "D107") (pin "1-VDD") (pinfunction "VDD_1-VDD") (pintype "power_in"))
      (node (ref "D108") (pin "1-VDD") (pinfunction "VDD_1-VDD") (pintype "power_in"))
      (node (ref "D109") (pin "1-VDD") (pinfunction "VDD_1-VDD") (pintype "power_in"))
      (node (ref "D110") (pin "1-VDD") (pinfunction "VDD_1-VDD") (pintype "power_in"))
      (node (ref "D111") (pin "1-VDD") (pinfunction "VDD_1-VDD") (pintype "power_in"))
      (node (ref "D112") (pin "1-VDD") (pinfunction "VDD_1-VDD") (pintype "power_in"))
      (node (ref "D113") (pin "1-VDD") (pinfunction "VDD_1-VDD") (pintype "power_in"))
      (node (ref "D114") (pin "1-VDD") (pinfunction "VDD_1-VDD") (pintype "power_in"))
      (node (ref "D115") (pin "1-VDD") (pinfunction "VDD_1-VDD") (pintype "power_in"))
      (node (ref "D116") (pin "1-VDD") (pinfunction "VDD_1-VDD") (pintype "power_in"))
      (node (ref "D117") (pin "1-VDD") (pinfunction "VDD_1-VDD") (pintype "power_in"))
      (node (ref "D118") (pin "1-VDD") (pinfunction "VDD_1-VDD") (pintype "power_in"))
      (node (ref "D119") (pin "1-VDD") (pinfunction "VDD_1-VDD") (pintype "power_in"))
      (node (ref "D120") (pin "1-VDD") (pinfunction "VDD_1-VDD") (pintype "power_in"))
      (node (ref "D121") (pin "1-VDD") (pinfunction "VDD_1-VDD") (pintype "power_in"))
      (node (ref "D122") (pin "1-VDD") (pinfunction "VDD_1-VDD") (pintype "power_in"))
      (node (ref "D123") (pin "1-VDD") (pinfunction "VDD_1-VDD") (pintype "power_in"))
      (node (ref "D124") (pin "1-VDD") (pinfunction "VDD_1-VDD") (pintype "power_in"))
      (node (ref "D125") (pin "1-VDD") (pinfunction "VDD_1-VDD") (pintype "power_in"))
      (node (ref "D126") (pin "1-VDD") (pinfunction "VDD_1-VDD") (pintype "power_in"))
      (node (ref "D127") (pin "1-VDD") (pinfunction "VDD_1-VDD") (pintype "power_in"))
      (node (ref "D128") (pin "1-VDD") (pinfunction "VDD_1-VDD") (pintype "power_in"))
      (node (ref "D129") (pin "1-VDD") (pinfunction "VDD_1-VDD") (pintype "power_in"))
      (node (ref "D130") (pin "1-VDD") (pinfunction "VDD_1-VDD") (pintype "power_in"))
      (node (ref "D131") (pin "1-VDD") (pinfunction "VDD_1-VDD") (pintype "power_in"))
      (node (ref "D132") (pin "1-VDD") (pinfunction "VDD_1-VDD") (pintype "power_in"))
      (node (ref "D133") (pin "1-VDD") (pinfunction "VDD_1-VDD") (pintype "power_in"))
      (node (ref "D134") (pin "1-VDD") (pinfunction "VDD_1-VDD") (pintype "power_in"))
      (node (ref "D135") (pin "1-VDD") (pinfunction "VDD_1-VDD") (pintype "power_in"))
      (node (ref "D136") (pin "1-VDD") (pinfunction "VDD_1-VDD") (pintype "power_in"))
      (node (ref "D137") (pin "1-VDD") (pinfunction "VDD_1-VDD") (pintype "power_in"))
      (node (ref "D138") (pin "1-VDD") (pinfunction "VDD_1-VDD") (pintype "power_in"))
      (node (ref "D139") (pin "1-VDD") (pinfunction "VDD_1-VDD") (pintype "power_in"))
      (node (ref "D140") (pin "1-VDD") (pinfunction "VDD_1-VDD") (pintype "power_in"))
      (node (ref "D141") (pin "1-VDD") (pinfunction "VDD_1-VDD") (pintype "power_in"))
      (node (ref "D142") (pin "1-VDD") (pinfunction "VDD_1-VDD") (pintype "power_in"))
      (node (ref "D143") (pin "1-VDD") (pinfunction "VDD_1-VDD") (pintype "power_in"))
      (node (ref "D144") (pin "1-VDD") (pinfunction "VDD_1-VDD") (pintype "power_in"))
      (node (ref "D97") (pin "1-VDD") (pinfunction "VDD_1-VDD") (pintype "power_in"))
      (node (ref "D98") (pin "1-VDD") (pinfunction "VDD_1-VDD") (pintype "power_in"))
      (node (ref "D99") (pin "1-VDD") (pinfunction "VDD_1-VDD") (pintype "power_in"))
    )
    (net (code "2") (name "/ROW_4_5") (class "Default")
      (node (ref "R6") (pin "2") (pinfunction "2_2") (pintype "passive"))
    )
    (net (code "3") (name "/ROW_6_7") (class "Default")
      (node (ref "D144") (pin "2-DOUT") (pinfunction "DO_2-DOUT") (pintype "output"))
    )
    (net (code "4") (name "/SIG3") (class "Default")
      (node (ref "R7") (pin "1") (pinfunction "1_1") (pintype "passive"))
    )
    (net (code "5") (name "GND") (class "Default")
      (node (ref "C100") (pin "1") (pinfunction "1_1") (pintype "passive"))
      (node (ref "C101") (pin "1") (pinfunction "1_1") (pintype "passive"))
      (node (ref "C102") (pin "1") (pinfunction "1_1") (pintype "passive"))
      (node (ref "C103") (pin "1") (pinfunction "1_1") (pintype "passive"))
      (node (ref "C104") (pin "1") (pinfunction "1_1") (pintype "passive"))
      (node (ref "C105") (pin "1") (pinfunction "1_1") (pintype "passive"))
      (node (ref "C106") (pin "1") (pinfunction "1_1") (pintype "passive"))
      (node (ref "C107") (pin "1") (pinfunction "1_1") (pintype "passive"))
      (node (ref "C108") (pin "1") (pinfunction "1_1") (pintype "passive"))
      (node (ref "C109") (pin "1") (pinfunction "1_1") (pintype "passive"))
      (node (ref "C110") (pin "1") (pinfunction "1_1") (pintype "passive"))
      (node (ref "C111") (pin "1") (pinfunction "1_1") (pintype "passive"))
      (node (ref "C112") (pin "1") (pinfunction "1_1") (pintype "passive"))
      (node (ref "C113") (pin "1") (pinfunction "1_1") (pintype "passive"))
      (node (ref "C114") (pin "1") (pinfunction "1_1") (pintype "passive"))
      (node (ref "C115") (pin "1") (pinfunction "1_1") (pintype "passive"))
      (node (ref "C116") (pin "1") (pinfunction "1_1") (pintype "passive"))
      (node (ref "C117") (pin "1") (pinfunction "1_1") (pintype "passive"))
      (node (ref "C118") (pin "1") (pinfunction "1_1") (pintype "passive"))
      (node (ref "C119") (pin "1") (pinfunction "1_1") (pintype "passive"))
      (node (ref "C120") (pin "1") (pinfunction "1_1") (pintype "passive"))
      (node (ref "C121") (pin "1") (pinfunction "1_1") (pintype "passive"))
      (node (ref "C122") (pin "1") (pinfunction "1_1") (pintype "passive"))
      (node (ref "C123") (pin "1") (pinfunction "1_1") (pintype "passive"))
      (node (ref "C124") (pin "1") (pinfunction "1_1") (pintype "passive"))
      (node (ref "C125") (pin "1") (pinfunction "1_1") (pintype "passive"))
      (node (ref "C126") (pin "1") (pinfunction "1_1") (pintype "passive"))
      (node (ref "C127") (pin "1") (pinfunction "1_1") (pintype "passive"))
      (node (ref "C128") (pin "1") (pinfunction "1_1") (pintype "passive"))
      (node (ref "C129") (pin "1") (pinfunction "1_1") (pintype "passive"))
      (node (ref "C130") (pin "1") (pinfunction "1_1") (pintype "passive"))
      (node (ref "C131") (pin "1") (pinfunction "1_1") (pintype "passive"))
      (node (ref "C132") (pin "1") (pinfunction "1_1") (pintype "passive"))
      (node (ref "C133") (pin "1") (pinfunction "1_1") (pintype "passive"))
      (node (ref "C134") (pin "1") (pinfunction "1_1") (pintype "passive"))
      (node (ref "C135") (pin "1") (pinfunction "1_1") (pintype "passive"))
      (node (ref "C136") (pin "1") (pinfunction "1_1") (pintype "passive"))
      (node (ref "C137") (pin "1") (pinfunction "1_1") (pintype "passive"))
      (node (ref "C138") (pin "1") (pinfunction "1_1") (pintype "passive"))
      (node (ref "C139") (pin "1") (pinfunction "1_1") (pintype "passive"))
      (node (ref "C140") (pin "1") (pinfunction "1_1") (pintype "passive"))
      (node (ref "C141") (pin "1") (pinfunction "1_1") (pintype "passive"))
      (node (ref "C142") (pin "1") (pinfunction "1_1") (pintype "passive"))
      (node (ref "C143") (pin "1") (pinfunction "1_1") (pintype "passive"))
      (node (ref "C144") (pin "1") (pinfunction "1_1") (pintype "passive"))
      (node (ref "C97") (pin "1") (pinfunction "1_1") (pintype "passive"))
      (node (ref "C98") (pin "1") (pinfunction "1_1") (pintype "passive"))
      (node (ref "C99") (pin "1") (pinfunction "1_1") (pintype "passive"))
      (node (ref "D100") (pin "3-GND") (pinfunction "GND_3-GND") (pintype "power_in"))
      (node (ref "D101") (pin "3-GND") (pinfunction "GND_3-GND") (pintype "power_in"))
      (node (ref "D102") (pin "3-GND") (pinfunction "GND_3-GND") (pintype "power_in"))
      (node (ref "D103") (pin "3-GND") (pinfunction "GND_3-GND") (pintype "power_in"))
      (node (ref "D104") (pin "3-GND") (pinfunction "GND_3-GND") (pintype "power_in"))
      (node (ref "D105") (pin "3-GND") (pinfunction "GND_3-GND") (pintype "power_in"))
      (node (ref "D106") (pin "3-GND") (pinfunction "GND_3-GND") (pintype "power_in"))
      (node (ref "D107") (pin "3-GND") (pinfunction "GND_3-GND") (pintype "power_in"))
      (node (ref "D108") (pin "3-GND") (pinfunction "GND_3-GND") (pintype "power_in"))
      (node (ref "D109") (pin "3-GND") (pinfunction "GND_3-GND") (pintype "power_in"))
      (node (ref "D110") (pin "3-GND") (pinfunction "GND_3-GND") (pintype "power_in"))
      (node (ref "D111") (pin "3-GND") (pinfunction "GND_3-GND") (pintype "power_in"))
      (node (ref "D112") (pin "3-GND") (pinfunction "GND_3-GND") (pintype "power_in"))
      (node (ref "D113") (pin "3-GND") (pinfunction "GND_3-GND") (pintype "power_in"))
      (node (ref "D114") (pin "3-GND") (pinfunction "GND_3-GND") (pintype "power_in"))
      (node (ref "D115") (pin "3-GND") (pinfunction "GND_3-GND") (pintype "power_in"))
      (node (ref "D116") (pin "3-GND") (pinfunction "GND_3-GND") (pintype "power_in"))
      (node (ref "D117") (pin "3-GND") (pinfunction "GND_3-GND") (pintype "power_in"))
      (node (ref "D118") (pin "3-GND") (pinfunction "GND_3-GND") (pintype "power_in"))
      (node (ref "D119") (pin "3-GND") (pinfunction "GND_3-GND") (pintype "power_in"))
      (node (ref "D120") (pin "3-GND") (pinfunction "GND_3-GND") (pintype "power_in"))
      (node (ref "D121") (pin "3-GND") (pinfunction "GND_3-GND") (pintype "power_in"))
      (node (ref "D122") (pin "3-GND") (pinfunction "GND_3-GND") (pintype "power_in"))
      (node (ref "D123") (pin "3-GND") (pinfunction "GND_3-GND") (pintype "power_in"))
      (node (ref "D124") (pin "3-GND") (pinfunction "GND_3-GND") (pintype "power_in"))
      (node (ref "D125") (pin "3-GND") (pinfunction "GND_3-GND") (pintype "power_in"))
      (node (ref "D126") (pin "3-GND") (pinfunction "GND_3-GND") (pintype "power_in"))
      (node (ref "D127") (pin "3-GND") (pinfunction "GND_3-GND") (pintype "power_in"))
      (node (ref "D128") (pin "3-GND") (pinfunction "GND_3-GND") (pintype "power_in"))
      (node (ref "D129") (pin "3-GND") (pinfunction "GND_3-GND") (pintype "power_in"))
      (node (ref "D130") (pin "3-GND") (pinfunction "GND_3-GND") (pintype "power_in"))
      (node (ref "D131") (pin "3-GND") (pinfunction "GND_3-GND") (pintype "power_in"))
      (node (ref "D132") (pin "3-GND") (pinfunction "GND_3-GND") (pintype "power_in"))
      (node (ref "D133") (pin "3-GND") (pinfunction "GND_3-GND") (pintype "power_in"))
      (node (ref "D134") (pin "3-GND") (pinfunction "GND_3-GND") (pintype "power_in"))
      (node (ref "D135") (pin "3-GND") (pinfunction "GND_3-GND") (pintype "power_in"))
      (node (ref "D136") (pin "3-GND") (pinfunction "GND_3-GND") (pintype "power_in"))
      (node (ref "D137") (pin "3-GND") (pinfunction "GND_3-GND") (pintype "power_in"))
      (node (ref "D138") (pin "3-GND") (pinfunction "GND_3-GND") (pintype "power_in"))
      (node (ref "D139") (pin "3-GND") (pinfunction "GND_3-GND") (pintype "power_in"))
      (node (ref "D140") (pin "3-GND") (pinfunction "GND_3-GND") (pintype "power_in"))
      (node (ref "D141") (pin "3-GND") (pinfunction "GND_3-GND") (pintype "power_in"))
      (node (ref "D142") (pin "3-GND") (pinfunction "GND_3-GND") (pintype "power_in"))
      (node (ref "D143") (pin "3-GND") (pinfunction "GND_3-GND") (pintype "power_in"))
      (node (ref "D144") (pin "3-GND") (pinfunction "GND_3-GND") (pintype "power_in"))
      (node (ref "D97") (pin "3-GND") (pinfunction "GND_3-GND") (pintype "power_in"))
      (node (ref "D98") (pin "3-GND") (pinfunction "GND_3-GND") (pintype "power_in"))
      (node (ref "D99") (pin "3-GND") (pinfunction "GND_3-GND") (pintype "power_in"))
    )
    (net (code "6") (name "Net-(D97-DI)") (class "Default")
      (node (ref "D97") (pin "4-DIN") (pinfunction "DI_4-DIN") (pintype "input"))
      (node (ref "R6") (pin "1") (pinfunction "1_1") (pintype "passive"))
      (node (ref "R7") (pin "2") (pinfunction "2_2") (pintype "passive"))
    )
    (net (code "7") (name "Net-(D97-DO)") (class "Default")
      (node (ref "D97") (pin "2-DOUT") (pinfunction "DO_2-DOUT") (pintype "output"))
      (node (ref "D98") (pin "4-DIN") (pinfunction "DI_4-DIN") (pintype "input"))
    )
    (net (code "8") (name "Net-(D98-DO)") (class "Default")
      (node (ref "D98") (pin "2-DOUT") (pinfunction "DO_2-DOUT") (pintype "output"))
      (node (ref "D99") (pin "4-DIN") (pinfunction "DI_4-DIN") (pintype "input"))
    )
    (net (code "9") (name "Net-(D100-DI)") (class "Default")
      (node (ref "D100") (pin "4-DIN") (pinfunction "DI_4-DIN") (pintype "input"))
      (node (ref "D99") (pin "2-DOUT") (pinfunction "DO_2-DOUT") (pintype "output"))
    )
    (net (code "10") (name "Net-(D100-DO)") (class "Default")
      (node (ref "D100") (pin "2-DOUT") (pinfunction "DO_2-DOUT") (pintype "output"))
      (node (ref "D101") (pin "4-DIN") (pinfunction "DI_4-DIN") (pintype "input"))
    )
    (net (code "11") (name "Net-(D101-DO)") (class "Default")
      (node (ref "D101") (pin "2-DOUT") (pinfunction "DO_2-DOUT") (pintype "output"))
      (node (ref "D102") (pin "4-DIN") (pinfunction "DI_4-DIN") (pintype "input"))
    )
    (net (code "12") (name "Net-(D102-DO)") (class "Default")
      (node (ref "D102") (pin "2-DOUT") (pinfunction "DO_2-DOUT") (pintype "output"))
      (node (ref "D103") (pin "4-DIN") (pinfunction "DI_4-DIN") (pintype "input"))
    )
    (net (code "13") (name "Net-(D103-DO)") (class "Default")
      (node (ref "D103") (pin "2-DOUT") (pinfunction "DO_2-DOUT") (pintype "output"))
      (node (ref "D104") (pin "4-DIN") (pinfunction "DI_4-DIN") (pintype "input"))
    )
    (net (code "14") (name "Net-(D104-DO)") (class "Default")
      (node (ref "D104") (pin "2-DOUT") (pinfunction "DO_2-DOUT") (pintype "output"))
      (node (ref "D105") (pin "4-DIN") (pinfunction "DI_4-DIN") (pintype "input"))
    )
    (net (code "15") (name "Net-(D105-DO)") (class "Default")
      (node (ref "D105") (pin "2-DOUT") (pinfunction "DO_2-DOUT") (pintype "output"))
      (node (ref "D106") (pin "4-DIN") (pinfunction "DI_4-DIN") (pintype "input"))
    )
    (net (code "16") (name "Net-(D106-DO)") (class "Default")
      (node (ref "D106") (pin "2-DOUT") (pinfunction "DO_2-DOUT") (pintype "output"))
      (node (ref "D107") (pin "4-DIN") (pinfunction "DI_4-DIN") (pintype "input"))
    )
    (net (code "17") (name "Net-(D107-DO)") (class "Default")
      (node (ref "D107") (pin "2-DOUT") (pinfunction "DO_2-DOUT") (pintype "output"))
      (node (ref "D108") (pin "4-DIN") (pinfunction "DI_4-DIN") (pintype "input"))
    )
    (net (code "18") (name "Net-(D108-DO)") (class "Default")
      (node (ref "D108") (pin "2-DOUT") (pinfunction "DO_2-DOUT") (pintype "output"))
      (node (ref "D109") (pin "4-DIN") (pinfunction "DI_4-DIN") (pintype "input"))
    )
    (net (code "19") (name "Net-(D109-DO)") (class "Default")
      (node (ref "D109") (pin "2-DOUT") (pinfunction "DO_2-DOUT") (pintype "output"))
      (node (ref "D110") (pin "4-DIN") (pinfunction "DI_4-DIN") (pintype "input"))
    )
    (net (code "20") (name "Net-(D110-DO)") (class "Default")
      (node (ref "D110") (pin "2-DOUT") (pinfunction "DO_2-DOUT") (pintype "output"))
      (node (ref "D111") (pin "4-DIN") (pinfunction "DI_4-DIN") (pintype "input"))
    )
    (net (code "21") (name "Net-(D111-DO)") (class "Default")
      (node (ref "D111") (pin "2-DOUT") (pinfunction "DO_2-DOUT") (pintype "output"))
      (node (ref "D112") (pin "4-DIN") (pinfunction "DI_4-DIN") (pintype "input"))
    )
    (net (code "22") (name "Net-(D112-DO)") (class "Default")
      (node (ref "D112") (pin "2-DOUT") (pinfunction "DO_2-DOUT") (pintype "output"))
      (node (ref "D113") (pin "4-DIN") (pinfunction "DI_4-DIN") (pintype "input"))
    )
    (net (code "23") (name "Net-(D113-DO)") (class "Default")
      (node (ref "D113") (pin "2-DOUT") (pinfunction "DO_2-DOUT") (pintype "output"))
      (node (ref "D114") (pin "4-DIN") (pinfunction "DI_4-DIN") (pintype "input"))
    )
    (net (code "24") (name "Net-(D114-DO)") (class "Default")
      (node (ref "D114") (pin "2-DOUT") (pinfunction "DO_2-DOUT") (pintype "output"))
      (node (ref "D115") (pin "4-DIN") (pinfunction "DI_4-DIN") (pintype "input"))
    )
    (net (code "25") (name "Net-(D115-DO)") (class "Default")
      (node (ref "D115") (pin "2-DOUT") (pinfunction "DO_2-DOUT") (pintype "output"))
      (node (ref "D116") (pin "4-DIN") (pinfunction "DI_4-DIN") (pintype "input"))
    )
    (net (code "26") (name "Net-(D116-DO)") (class "Default")
      (node (ref "D116") (pin "2-DOUT") (pinfunction "DO_2-DOUT") (pintype "output"))
      (node (ref "D117") (pin "4-DIN") (pinfunction "DI_4-DIN") (pintype "input"))
    )
    (net (code "27") (name "Net-(D117-DO)") (class "Default")
      (node (ref "D117") (pin "2-DOUT") (pinfunction "DO_2-DOUT") (pintype "output"))
      (node (ref "D118") (pin "4-DIN") (pinfunction "DI_4-DIN") (pintype "input"))
    )
    (net (code "28") (name "Net-(D118-DO)") (class "Default")
      (node (ref "D118") (pin "2-DOUT") (pinfunction "DO_2-DOUT") (pintype "output"))
      (node (ref "D119") (pin "4-DIN") (pinfunction "DI_4-DIN") (pintype "input"))
    )
    (net (code "29") (name "Net-(D119-DO)") (class "Default")
      (node (ref "D119") (pin "2-DOUT") (pinfunction "DO_2-DOUT") (pintype "output"))
      (node (ref "D120") (pin "4-DIN") (pinfunction "DI_4-DIN") (pintype "input"))
    )
    (net (code "30") (name "Net-(D120-DO)") (class "Default")
      (node (ref "D120") (pin "2-DOUT") (pinfunction "DO_2-DOUT") (pintype "output"))
      (node (ref "R8") (pin "2") (pinfunction "2_2") (pintype "passive"))
    )
    (net (code "31") (name "Net-(D121-DI)") (class "Default")
      (node (ref "D121") (pin "4-DIN") (pinfunction "DI_4-DIN") (pintype "input"))
      (node (ref "R8") (pin "1") (pinfunction "1_1") (pintype "passive"))
    )
    (net (code "32") (name "Net-(D121-DO)") (class "Default")
      (node (ref "D121") (pin "2-DOUT") (pinfunction "DO_2-DOUT") (pintype "output"))
      (node (ref "D122") (pin "4-DIN") (pinfunction "DI_4-DIN") (pintype "input"))
    )
    (net (code "33") (name "Net-(D122-DO)") (class "Default")
      (node (ref "D122") (pin "2-DOUT") (pinfunction "DO_2-DOUT") (pintype "output"))
      (node (ref "D123") (pin "4-DIN") (pinfunction "DI_4-DIN") (pintype "input"))
    )
    (net (code "34") (name "Net-(D123-DO)") (class "Default")
      (node (ref "D123") (pin "2-DOUT") (pinfunction "DO_2-DOUT") (pintype "output"))
      (node (ref "D124") (pin "4-DIN") (pinfunction "DI_4-DIN") (pintype "input"))
    )
    (net (code "35") (name "Net-(D124-DO)") (class "Default")
      (node (ref "D124") (pin "2-DOUT") (pinfunction "DO_2-DOUT") (pintype "output"))
      (node (ref "D125") (pin "4-DIN") (pinfunction "DI_4-DIN") (pintype "input"))
    )
    (net (code "36") (name "Net-(D125-DO)") (class "Default")
      (node (ref "D125") (pin "2-DOUT") (pinfunction "DO_2-DOUT") (pintype "output"))
      (node (ref "D126") (pin "4-DIN") (pinfunction "DI_4-DIN") (pintype "input"))
    )
    (net (code "37") (name "Net-(D126-DO)") (class "Default")
      (node (ref "D126") (pin "2-DOUT") (pinfunction "DO_2-DOUT") (pintype "output"))
      (node (ref "D127") (pin "4-DIN") (pinfunction "DI_4-DIN") (pintype "input"))
    )
    (net (code "38") (name "Net-(D127-DO)") (class "Default")
      (node (ref "D127") (pin "2-DOUT") (pinfunction "DO_2-DOUT") (pintype "output"))
      (node (ref "D128") (pin "4-DIN") (pinfunction "DI_4-DIN") (pintype "input"))
    )
    (net (code "39") (name "Net-(D128-DO)") (class "Default")
      (node (ref "D128") (pin "2-DOUT") (pinfunction "DO_2-DOUT") (pintype "output"))
      (node (ref "D129") (pin "4-DIN") (pinfunction "DI_4-DIN") (pintype "input"))
    )
    (net (code "40") (name "Net-(D129-DO)") (class "Default")
      (node (ref "D129") (pin "2-DOUT") (pinfunction "DO_2-DOUT") (pintype "output"))
      (node (ref "D130") (pin "4-DIN") (pinfunction "DI_4-DIN") (pintype "input"))
    )
    (net (code "41") (name "Net-(D130-DO)") (class "Default")
      (node (ref "D130") (pin "2-DOUT") (pinfunction "DO_2-DOUT") (pintype "output"))
      (node (ref "D131") (pin "4-DIN") (pinfunction "DI_4-DIN") (pintype "input"))
    )
    (net (code "42") (name "Net-(D131-DO)") (class "Default")
      (node (ref "D131") (pin "2-DOUT") (pinfunction "DO_2-DOUT") (pintype "output"))
      (node (ref "D132") (pin "4-DIN") (pinfunction "DI_4-DIN") (pintype "input"))
    )
    (net (code "43") (name "Net-(D132-DO)") (class "Default")
      (node (ref "D132") (pin "2-DOUT") (pinfunction "DO_2-DOUT") (pintype "output"))
      (node (ref "D133") (pin "4-DIN") (pinfunction "DI_4-DIN") (pintype "input"))
    )
    (net (code "44") (name "Net-(D133-DO)") (class "Default")
      (node (ref "D133") (pin "2-DOUT") (pinfunction "DO_2-DOUT") (pintype "output"))
      (node (ref "D134") (pin "4-DIN") (pinfunction "DI_4-DIN") (pintype "input"))
    )
    (net (code "45") (name "Net-(D134-DO)") (class "Default")
      (node (ref "D134") (pin "2-DOUT") (pinfunction "DO_2-DOUT") (pintype "output"))
      (node (ref "D135") (pin "4-DIN") (pinfunction "DI_4-DIN") (pintype "input"))
    )
    (net (code "46") (name "Net-(D135-DO)") (class "Default")
      (node (ref "D135") (pin "2-DOUT") (pinfunction "DO_2-DOUT") (pintype "output"))
      (node (ref "D136") (pin "4-DIN") (pinfunction "DI_4-DIN") (pintype "input"))
    )
    (net (code "47") (name "Net-(D136-DO)") (class "Default")
      (node (ref "D136") (pin "2-DOUT") (pinfunction "DO_2-DOUT") (pintype "output"))
      (node (ref "D137") (pin "4-DIN") (pinfunction "DI_4-DIN") (pintype "input"))
    )
    (net (code "48") (name "Net-(D137-DO)") (class "Default")
      (node (ref "D137") (pin "2-DOUT") (pinfunction "DO_2-DOUT") (pintype "output"))
      (node (ref "D138") (pin "4-DIN") (pinfunction "DI_4-DIN") (pintype "input"))
    )
    (net (code "49") (name "Net-(D138-DO)") (class "Default")
      (node (ref "D138") (pin "2-DOUT") (pinfunction "DO_2-DOUT") (pintype "output"))
      (node (ref "D139") (pin "4-DIN") (pinfunction "DI_4-DIN") (pintype "input"))
    )
    (net (code "50") (name "Net-(D139-DO)") (class "Default")
      (node (ref "D139") (pin "2-DOUT") (pinfunction "DO_2-DOUT") (pintype "output"))
      (node (ref "D140") (pin "4-DIN") (pinfunction "DI_4-DIN") (pintype "input"))
    )
    (net (code "51") (name "Net-(D140-DO)") (class "Default")
      (node (ref "D140") (pin "2-DOUT") (pinfunction "DO_2-DOUT") (pintype "output"))
      (node (ref "D141") (pin "4-DIN") (pinfunction "DI_4-DIN") (pintype "input"))
    )
    (net (code "52") (name "Net-(D141-DO)") (class "Default")
      (node (ref "D141") (pin "2-DOUT") (pinfunction "DO_2-DOUT") (pintype "output"))
      (node (ref "D142") (pin "4-DIN") (pinfunction "DI_4-DIN") (pintype "input"))
    )
    (net (code "53") (name "Net-(D142-DO)") (class "Default")
      (node (ref "D142") (pin "2-DOUT") (pinfunction "DO_2-DOUT") (pintype "output"))
      (node (ref "D143") (pin "4-DIN") (pinfunction "DI_4-DIN") (pintype "input"))
    )
    (net (code "54") (name "Net-(D143-DO)") (class "Default")
      (node (ref "D143") (pin "2-DOUT") (pinfunction "DO_2-DOUT") (pintype "output"))
      (node (ref "D144") (pin "4-DIN") (pinfunction "DI_4-DIN") (pintype "input"))
    )
  )
)
